# 10_-MAIN_POWER.net
KiCad netlist of a schematic drawn in Altium Designer
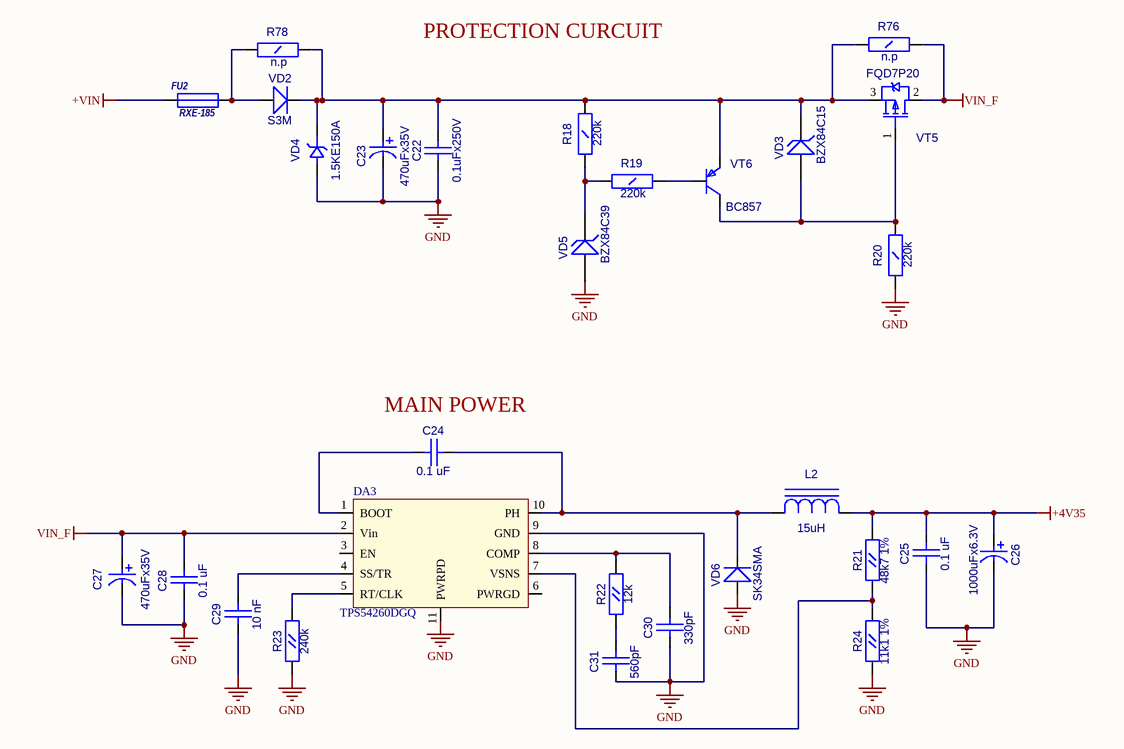
[diagram p0: [10]-MAIN_POWER.SchDoc]

(export (version "E")
  (design (tool "Eeschema 10.0.6"))
  (components
    (comp (ref "C22")
      (value "0.1uFx250V")
      (footprint "CC1206")
      (description "CC1206")
      (libsource (lib "gprs_modem_2") (part "CC1206"))
    )
    (comp (ref "C23")
      (value "470uFx35V")
      (footprint "CC16X10_CAP0.5(1)(Primary)")
      (description "CAP0.5(1)")
      (libsource (lib "gprs_modem_2") (part "CAP0.5(1)"))
    )
    (comp (ref "C24")
      (value "0.1 uF")
      (footprint "CC0603")
      (description "CC0603")
      (libsource (lib "gprs_modem_2") (part "CC0603"))
    )
    (comp (ref "C25")
      (value "0.1 uF")
      (footprint "CC0603")
      (description "CC0603")
      (libsource (lib "gprs_modem_2") (part "CC0603"))
    )
    (comp (ref "C26")
      (value "1000uFx6.3V")
      (footprint "CC8X3.5")
      (description "CAP0.35")
      (libsource (lib "gprs_modem_2") (part "CAP0.35"))
    )
    (comp (ref "C27")
      (value "470uFx35V")
      (footprint "CC16X10_CAP0.5(1)(Primary)")
      (description "CAP0.5(1)")
      (libsource (lib "gprs_modem_2") (part "CAP0.5(1)"))
    )
    (comp (ref "C28")
      (value "0.1 uF")
      (footprint "CC0603")
      (description "CC0603")
      (libsource (lib "gprs_modem_2") (part "CC0603"))
    )
    (comp (ref "C29")
      (value "10 nF")
      (footprint "CC0603")
      (description "CC0603")
      (libsource (lib "gprs_modem_2") (part "CC0603"))
    )
    (comp (ref "C30")
      (value "330pF")
      (footprint "CC0603")
      (description "CC0603")
      (libsource (lib "gprs_modem_2") (part "CC0603"))
    )
    (comp (ref "C31")
      (value "560pF")
      (footprint "CC0603")
      (description "CC0603")
      (libsource (lib "gprs_modem_2") (part "CC0603"))
    )
    (comp (ref "DA3")
      (value "TPS54260DGQ")
      (footprint "S-PDSO-G10")
      (libsource (lib "gprs_modem_2") (part "TPS54260DGQ"))
    )
    (comp (ref "FU2") (value "RXE-185") (footprint "RXE-185") (libsource (lib "fizik_lib") (part "RXE-185")))
    (comp (ref "L2")
      (value "15uH")
      (footprint "SDR0805")
      (description "SDR0805")
      (libsource (lib "gprs_modem_2") (part "SDR0805"))
    )
    (comp (ref "R18")
      (value "220k")
      (footprint "RC1206")
      (description "RC1206")
      (libsource (lib "fizik_lib") (part "RC1206"))
    )
    (comp (ref "R19")
      (value "220k")
      (footprint "RC1206")
      (description "RC1206")
      (libsource (lib "fizik_lib") (part "RC1206"))
    )
    (comp (ref "R20")
      (value "220k")
      (footprint "RC1206")
      (description "RC1206")
      (libsource (lib "fizik_lib") (part "RC1206"))
    )
    (comp (ref "R21")
      (value "48k7 1%")
      (footprint "RC0603")
      (description "RC0603")
      (libsource (lib "gprs_modem_2") (part "RC0603"))
    )
    (comp (ref "R22")
      (value "12k")
      (footprint "RC0603")
      (description "RC0603")
      (libsource (lib "gprs_modem_2") (part "RC0603"))
    )
    (comp (ref "R23")
      (value "240k")
      (footprint "RC0603")
      (description "RC0603")
      (libsource (lib "gprs_modem_2") (part "RC0603"))
    )
    (comp (ref "R24")
      (value "11k1 1%")
      (footprint "RC0603")
      (description "RC0603")
      (libsource (lib "gprs_modem_2") (part "RC0603"))
    )
    (comp (ref "R76")
      (value "n.p")
      (footprint "RC1206")
      (description "RC1206")
      (libsource (lib "fizik_lib") (part "RC1206"))
    )
    (comp (ref "R78")
      (value "n.p")
      (footprint "RC1206")
      (description "RC1206")
      (libsource (lib "fizik_lib") (part "RC1206"))
    )
    (comp (ref "VD2")
      (value "S3M")
      (footprint "SMC")
      (description "Schottky Rectifier")
      (libsource (lib "fizik_lib") (part "S3A"))
    )
    (comp (ref "VD3")
      (value "BZX84C15")
      (footprint "SOT-23(123)")
      (description "Zener Voltage Regulator Diode")
      (libsource (lib "fizik_lib") (part "BZX84"))
    )
    (comp (ref "VD4")
      (value "1.5KE150A")
      (footprint "DO-201")
      (description "1.5KE")
      (libsource (lib "gprs_modem") (part "1.5KE"))
    )
    (comp (ref "VD5")
      (value "BZX84C39")
      (footprint "SOT-23(123)")
      (description "Zener Voltage Regulator Diode")
      (libsource (lib "fizik_lib") (part "BZX84"))
    )
    (comp (ref "VD6")
      (value "SK34SMA")
      (footprint "SMA")
      (description "Schottky Rectifier")
      (libsource (lib "gprs_modem") (part "SK34SMA"))
    )
    (comp (ref "VT5")
      (value "FQD7P20")
      (footprint "D-PAK(TO-252AA)")
      (description "HEXFET Power MOSFET")
      (libsource (lib "gprs_modem_2") (part "IRFR9220"))
    )
    (comp (ref "VT6")
      (value "BC857")
      (footprint "SOT-23(123)")
      (description "PNP 100ma transistor")
      (libsource (lib "gprs_modem_2") (part "BC857B"))
    )
  )
  (nets
    (net (code "1") (name "+4V35") (class "Default")
      (node (ref "C25") (pin "1") (pinfunction "A_1") (pintype "passive"))
      (node (ref "C26") (pin "1") (pintype "passive"))
      (node (ref "L2") (pin "2") (pinfunction "A_2") (pintype "passive"))
      (node (ref "R21") (pin "2") (pinfunction "B_2") (pintype "passive"))
    )
    (net (code "2") (name "+VIN") (class "Default") (node (ref "FU2") (pin "1") (pintype "passive")))
    (net (code "3") (name "GND") (class "Default")
      (node (ref "C22") (pin "1") (pinfunction "A_1") (pintype "passive"))
      (node (ref "C23") (pin "1") (pintype "passive"))
      (node (ref "C25") (pin "2") (pinfunction "B_2") (pintype "passive"))
      (node (ref "C26") (pin "2") (pintype "passive"))
      (node (ref "C27") (pin "1") (pintype "passive"))
      (node (ref "C28") (pin "2") (pinfunction "B_2") (pintype "passive"))
      (node (ref "C29") (pin "2") (pinfunction "B_2") (pintype "passive"))
      (node (ref "C30") (pin "2") (pinfunction "B_2") (pintype "passive"))
      (node (ref "C31") (pin "2") (pinfunction "B_2") (pintype "passive"))
      (node (ref "DA3") (pin "11") (pinfunction "PWRPD_11") (pintype "passive"))
      (node (ref "DA3") (pin "9") (pinfunction "GND_9") (pintype "passive"))
      (node (ref "R20") (pin "1") (pinfunction "A_1") (pintype "passive"))
      (node (ref "R23") (pin "1") (pinfunction "A_1") (pintype "passive"))
      (node (ref "R24") (pin "1") (pinfunction "A_1") (pintype "passive"))
      (node (ref "VD4") (pin "1") (pinfunction "A_1") (pintype "passive"))
      (node (ref "VD5") (pin "1") (pinfunction "A_1") (pintype "passive"))
      (node (ref "VD6") (pin "1") (pinfunction "A_1") (pintype "passive"))
    )
    (net (code "4") (name "Net-(C22-B)") (class "Default")
      (node (ref "C22") (pin "2") (pinfunction "B_2") (pintype "passive"))
      (node (ref "C23") (pin "2") (pintype "passive"))
      (node (ref "R18") (pin "2") (pinfunction "B_2") (pintype "passive"))
      (node (ref "R76") (pin "1") (pinfunction "A_1") (pintype "passive"))
      (node (ref "R78") (pin "2") (pinfunction "B_2") (pintype "passive"))
      (node (ref "VD2") (pin "2") (pinfunction "K_2") (pintype "passive"))
      (node (ref "VD3") (pin "3") (pinfunction "K_3") (pintype "passive"))
      (node (ref "VD4") (pin "2") (pinfunction "K_2") (pintype "passive"))
      (node (ref "VT5") (pin "3") (pinfunction "S_3") (pintype "passive"))
      (node (ref "VT6") (pin "2") (pinfunction "E_2") (pintype "passive"))
    )
    (net (code "5") (name "Net-(C24-A)") (class "Default")
      (node (ref "C24") (pin "1") (pinfunction "A_1") (pintype "passive"))
      (node (ref "DA3") (pin "10") (pinfunction "PH_10") (pintype "passive"))
      (node (ref "L2") (pin "1") (pinfunction "C_1") (pintype "passive"))
      (node (ref "VD6") (pin "2") (pinfunction "K_2") (pintype "passive"))
    )
    (net (code "6") (name "Net-(C24-B)") (class "Default")
      (node (ref "C24") (pin "2") (pinfunction "B_2") (pintype "passive"))
      (node (ref "DA3") (pin "1") (pinfunction "BOOT_1") (pintype "passive"))
    )
    (net (code "7") (name "Net-(C29-A)") (class "Default")
      (node (ref "C29") (pin "1") (pinfunction "A_1") (pintype "passive"))
      (node (ref "DA3") (pin "4") (pinfunction "SS/TR_4") (pintype "passive"))
    )
    (net (code "8") (name "Net-(C30-A)") (class "Default")
      (node (ref "C30") (pin "1") (pinfunction "A_1") (pintype "passive"))
      (node (ref "DA3") (pin "8") (pinfunction "COMP_8") (pintype "passive"))
      (node (ref "R22") (pin "2") (pinfunction "B_2") (pintype "passive"))
    )
    (net (code "9") (name "Net-(C31-A)") (class "Default")
      (node (ref "C31") (pin "1") (pinfunction "A_1") (pintype "passive"))
      (node (ref "R22") (pin "1") (pinfunction "A_1") (pintype "passive"))
    )
    (net (code "10") (name "Net-(DA3-RT{slash}CLK)") (class "Default")
      (node (ref "DA3") (pin "5") (pinfunction "RT/CLK_5") (pintype "passive"))
      (node (ref "R23") (pin "2") (pinfunction "B_2") (pintype "passive"))
    )
    (net (code "11") (name "Net-(DA3-VSNS)") (class "Default")
      (node (ref "DA3") (pin "7") (pinfunction "VSNS_7") (pintype "passive"))
      (node (ref "R21") (pin "1") (pinfunction "A_1") (pintype "passive"))
      (node (ref "R24") (pin "2") (pinfunction "B_2") (pintype "passive"))
    )
    (net (code "12") (name "Net-(R18-A)") (class "Default")
      (node (ref "R18") (pin "1") (pinfunction "A_1") (pintype "passive"))
      (node (ref "R19") (pin "1") (pinfunction "A_1") (pintype "passive"))
      (node (ref "VD5") (pin "3") (pinfunction "K_3") (pintype "passive"))
    )
    (net (code "13") (name "Net-(R19-B)") (class "Default")
      (node (ref "R19") (pin "2") (pinfunction "B_2") (pintype "passive"))
      (node (ref "VT6") (pin "1") (pinfunction "B_1") (pintype "passive"))
    )
    (net (code "14") (name "Net-(R20-B)") (class "Default")
      (node (ref "R20") (pin "2") (pinfunction "B_2") (pintype "passive"))
      (node (ref "VD3") (pin "1") (pinfunction "A_1") (pintype "passive"))
      (node (ref "VT5") (pin "1") (pinfunction "G_1") (pintype "passive"))
      (node (ref "VT6") (pin "3") (pinfunction "C_3") (pintype "passive"))
    )
    (net (code "15") (name "Net-(R78-A)") (class "Default")
      (node (ref "FU2") (pin "2") (pintype "passive"))
      (node (ref "R78") (pin "1") (pinfunction "A_1") (pintype "passive"))
      (node (ref "VD2") (pin "1") (pinfunction "A_1") (pintype "passive"))
    )
    (net (code "16") (name "VIN_F") (class "Default")
      (node (ref "C27") (pin "2") (pintype "passive"))
      (node (ref "C28") (pin "1") (pinfunction "A_1") (pintype "passive"))
      (node (ref "DA3") (pin "2") (pinfunction "Vin_2") (pintype "passive"))
      (node (ref "R76") (pin "2") (pinfunction "B_2") (pintype "passive"))
      (node (ref "VT5") (pin "2") (pinfunction "D_2") (pintype "passive"))
    )
    (net (code "17") (name "unconnected-(DA3-EN-Pad3)") (class "Default")
      (node (ref "DA3") (pin "3") (pinfunction "EN_3") (pintype "passive"))
    )
    (net (code "18") (name "unconnected-(DA3-PWRGD-Pad6)") (class "Default")
      (node (ref "DA3") (pin "6") (pinfunction "PWRGD_6") (pintype "passive"))
    )
  )
)
